# Nguon_MIC_Sch.net
KiCad netlist of a schematic drawn in Altium Designer
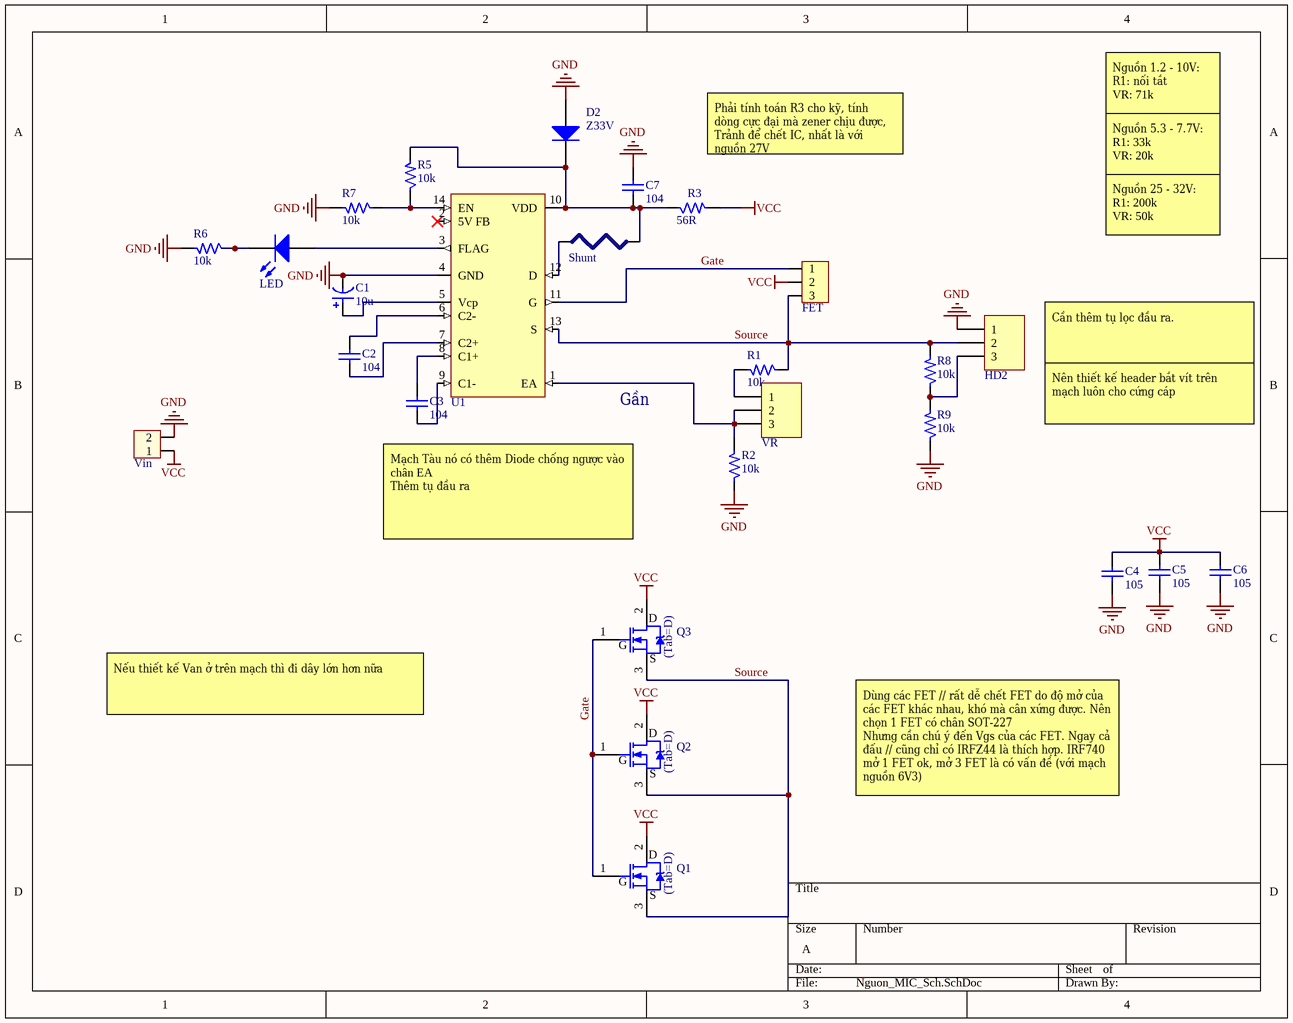
[diagram p0: Nguon_MIC_Sch.SchDoc]

(export (version "E")
  (design (tool "Eeschema 10.0.6"))
  (components
    (comp (ref "C1")
      (value "10u")
      (footprint "C5mm")
      (description "Cap pol")
      (fields (field (name "Comment") "Cap Pol1") (field (name "PUBLISHER") "Altium Limited"))
      (libsource (lib "hienclubvn") (part "Cap Pol"))
    )
    (comp (ref "C2")
      (value "104")
      (footprint "CN1.5")
      (description "Capacitor")
      (fields (field (name "Comment") "Cap") (field (name "PUBLISHER") "Altium Limited"))
      (libsource (lib "hienclubvn") (part "Cap"))
    )
    (comp (ref "C3")
      (value "104")
      (footprint "CN1.5")
      (description "Capacitor")
      (fields (field (name "Comment") "Cap") (field (name "PUBLISHER") "Altium Limited"))
      (libsource (lib "hienclubvn") (part "Cap"))
    )
    (comp (ref "C4")
      (value "105")
      (footprint "CN1.5")
      (description "Capacitor")
      (fields (field (name "Comment") "Cap") (field (name "PUBLISHER") "Altium Limited"))
      (libsource (lib "hienclubvn") (part "Cap"))
    )
    (comp (ref "C5")
      (value "105")
      (footprint "CN1.5")
      (description "Capacitor")
      (fields (field (name "Comment") "Cap") (field (name "PUBLISHER") "Altium Limited"))
      (libsource (lib "hienclubvn") (part "Cap"))
    )
    (comp (ref "C6")
      (value "105")
      (footprint "CN1.5")
      (description "Capacitor")
      (fields (field (name "Comment") "Cap") (field (name "PUBLISHER") "Altium Limited"))
      (libsource (lib "hienclubvn") (part "Cap"))
    )
    (comp (ref "C7")
      (value "104")
      (footprint "CN1.5")
      (description "Capacitor")
      (fields (field (name "Comment") "Cap") (field (name "PUBLISHER") "Altium Limited"))
      (libsource (lib "hienclubvn") (part "Cap"))
    )
    (comp (ref "D2")
      (value "Z33V")
      (footprint "1N4148")
      (description "Default Diode")
      (fields (field (name "PUBLISHER") "Altium Limited"))
      (libsource (lib "hienclubvn") (part "Diode"))
    )
    (comp (ref "FET")
      (value "Header 3")
      (footprint "Header 3 - 150mil")
      (libsource (lib "TIEP2013") (part "Header 3"))
    )
    (comp (ref "HD2")
      (value "Header 3")
      (footprint "BIG_Header 3")
      (description "Header, 3-Pin")
      (fields (field (name "PUBLISHER") "Altium Limited"))
      (libsource (lib "hienclubvn") (part "Header 3"))
    )
    (comp (ref "LED")
      (value "LED SMD")
      (footprint "LED_0805_Blue")
      (description "LED")
      (libsource (lib "PIF_Library") (part "LED SMD"))
    )
    (comp (ref "Q1")
      (value "IRF3205")
      (footprint "TO-220")
      (description "HEXFET N-Channel Power MOSFET")
      (libsource (lib "HIENCLUBVN_Library") (part "IRF3205"))
    )
    (comp (ref "Q2")
      (value "IRF3205")
      (footprint "TO-220")
      (description "HEXFET N-Channel Power MOSFET")
      (libsource (lib "HIENCLUBVN_Library") (part "IRF3205"))
    )
    (comp (ref "Q3")
      (value "IRF3205")
      (footprint "TO-220")
      (description "HEXFET N-Channel Power MOSFET")
      (libsource (lib "HIENCLUBVN_Library") (part "IRF3205"))
    )
    (comp (ref "R1")
      (value "10k")
      (footprint "SM-0805")
      (description "RES SMD 10K OHM 5% 1/8W 0805")
      (fields
        (field (name "MANUFACTURER") "Stackpole Electronics Inc.")
        (field (name "MANUFACTURER PART NUMBER") "RMCF0805JT10K0")
        (field (name "RESISTANCE (OHMS)") "10k")
      )
      (libsource (lib "HIENCLUBVN_Library") (part "RES 0805"))
    )
    (comp (ref "R2")
      (value "10k")
      (footprint "SM-0805")
      (description "RES SMD 10K OHM 5% 1/8W 0805")
      (fields
        (field (name "MANUFACTURER") "Stackpole Electronics Inc.")
        (field (name "MANUFACTURER PART NUMBER") "RMCF0805JT10K0")
        (field (name "RESISTANCE (OHMS)") "10k")
      )
      (libsource (lib "HIENCLUBVN_Library") (part "RES 0805"))
    )
    (comp (ref "R3")
      (value "56R")
      (footprint "R2W")
      (description "RES DIP 10K OHM 5% 1/4W")
      (fields
        (field (name "MANUFACTURER") "Stackpole Electronics Inc.")
        (field (name "MANUFACTURER PART NUMBER") "RMCF0805JT10K0")
        (field (name "RESISTANCE (OHMS)") "56R")
      )
      (libsource (lib "HIENCLUBVN_Library") (part "RES DIP"))
    )
    (comp (ref "R5")
      (value "10k")
      (footprint "SM-0805")
      (description "RES SMD 10K OHM 5% 1/8W 0805")
      (fields
        (field (name "MANUFACTURER") "Stackpole Electronics Inc.")
        (field (name "MANUFACTURER PART NUMBER") "RMCF0805JT10K0")
        (field (name "RESISTANCE (OHMS)") "10k")
      )
      (libsource (lib "HIENCLUBVN_Library") (part "RES 0805"))
    )
    (comp (ref "R6")
      (value "10k")
      (footprint "SM-0805")
      (description "RES SMD 10K OHM 5% 1/8W 0805")
      (fields
        (field (name "MANUFACTURER") "Stackpole Electronics Inc.")
        (field (name "MANUFACTURER PART NUMBER") "RMCF0805JT10K0")
        (field (name "RESISTANCE (OHMS)") "10k")
      )
      (libsource (lib "HIENCLUBVN_Library") (part "RES 0805"))
    )
    (comp (ref "R7")
      (value "10k")
      (footprint "SM-0805")
      (description "RES SMD 10K OHM 5% 1/8W 0805")
      (fields
        (field (name "MANUFACTURER") "Stackpole Electronics Inc.")
        (field (name "MANUFACTURER PART NUMBER") "RMCF0805JT10K0")
        (field (name "RESISTANCE (OHMS)") "10k")
      )
      (libsource (lib "HIENCLUBVN_Library") (part "RES 0805"))
    )
    (comp (ref "R8")
      (value "10k")
      (footprint "SM-0805")
      (description "RES SMD 10K OHM 5% 1/8W 0805")
      (fields
        (field (name "MANUFACTURER") "Stackpole Electronics Inc.")
        (field (name "MANUFACTURER PART NUMBER") "RMCF0805JT10K0")
        (field (name "RESISTANCE (OHMS)") "10k")
      )
      (libsource (lib "HIENCLUBVN_Library") (part "RES 0805"))
    )
    (comp (ref "R9")
      (value "10k")
      (footprint "SM-0805")
      (description "RES SMD 10K OHM 5% 1/8W 0805")
      (fields
        (field (name "MANUFACTURER") "Stackpole Electronics Inc.")
        (field (name "MANUFACTURER PART NUMBER") "RMCF0805JT10K0")
        (field (name "RESISTANCE (OHMS)") "10k")
      )
      (libsource (lib "HIENCLUBVN_Library") (part "RES 0805"))
    )
    (comp (ref "Shunt") (value "Shunt") (footprint "Shunt 5mR") (libsource (lib "TIEP2013") (part "Shunt")))
    (comp (ref "U1")
      (value "MIC5158")
      (footprint "SOIC14")
      (description "Super LDO")
      (libsource (lib "TIEP2013") (part "MIC5158"))
    )
    (comp (ref "Vin")
      (value "Header 2")
      (footprint "HEAD2T")
      (description "Header, 2-Pin")
      (libsource (lib "hienclubvn") (part "Header 2"))
    )
    (comp (ref "VR")
      (value "Header 3")
      (footprint "BIG_Header 3")
      (description "Header, 3-Pin")
      (fields (field (name "PUBLISHER") "Altium Limited"))
      (libsource (lib "hienclubvn") (part "Header 3"))
    )
  )
  (nets
    (net (code "1") (name "/Gate") (class "Default")
      (node (ref "FET") (pin "1") (pinfunction "1_1") (pintype "passive"))
      (node (ref "Q1") (pin "1") (pinfunction "G_1") (pintype "passive"))
      (node (ref "Q2") (pin "1") (pinfunction "G_1") (pintype "passive"))
      (node (ref "Q3") (pin "1") (pinfunction "G_1") (pintype "passive"))
      (node (ref "U1") (pin "11") (pinfunction "G_11") (pintype "output"))
    )
    (net (code "2") (name "/Source") (class "Default")
      (node (ref "FET") (pin "3") (pinfunction "3_3") (pintype "passive"))
      (node (ref "HD2") (pin "2") (pinfunction "2_2") (pintype "passive"))
      (node (ref "Q1") (pin "3") (pinfunction "S_3") (pintype "passive"))
      (node (ref "Q2") (pin "3") (pinfunction "S_3") (pintype "passive"))
      (node (ref "Q3") (pin "3") (pinfunction "S_3") (pintype "passive"))
      (node (ref "R1") (pin "1") (pinfunction "1_1") (pintype "passive"))
      (node (ref "R8") (pin "2") (pinfunction "2_2") (pintype "passive"))
      (node (ref "U1") (pin "13") (pinfunction "S_13") (pintype "input"))
    )
    (net (code "3") (name "GND") (class "Default")
      (node (ref "C1") (pin "2") (pinfunction "2_2") (pintype "passive"))
      (node (ref "C4") (pin "1") (pinfunction "1_1") (pintype "passive"))
      (node (ref "C5") (pin "1") (pinfunction "1_1") (pintype "passive"))
      (node (ref "C6") (pin "1") (pinfunction "1_1") (pintype "passive"))
      (node (ref "C7") (pin "2") (pinfunction "2_2") (pintype "passive"))
      (node (ref "D2") (pin "1") (pinfunction "A_1") (pintype "passive"))
      (node (ref "HD2") (pin "1") (pinfunction "1_1") (pintype "passive"))
      (node (ref "R2") (pin "1") (pinfunction "1_1") (pintype "passive"))
      (node (ref "R6") (pin "2") (pinfunction "2_2") (pintype "passive"))
      (node (ref "R7") (pin "2") (pinfunction "2_2") (pintype "passive"))
      (node (ref "R9") (pin "1") (pinfunction "1_1") (pintype "passive"))
      (node (ref "U1") (pin "4") (pinfunction "GND_4") (pintype "power_in"))
      (node (ref "Vin") (pin "2") (pinfunction "2_2") (pintype "passive"))
    )
    (net (code "4") (name "Net-(D2-K)") (class "Default")
      (node (ref "C7") (pin "1") (pinfunction "1_1") (pintype "passive"))
      (node (ref "D2") (pin "2") (pinfunction "K_2") (pintype "passive"))
      (node (ref "R3") (pin "1") (pinfunction "1_1") (pintype "passive"))
      (node (ref "R5") (pin "2") (pinfunction "2_2") (pintype "passive"))
      (node (ref "Shunt") (pin "1") (pinfunction "1_1") (pintype "passive"))
      (node (ref "U1") (pin "10") (pinfunction "VDD_10") (pintype "power_in"))
    )
    (net (code "5") (name "Net-(HD2-Pad3)") (class "Default")
      (node (ref "HD2") (pin "3") (pinfunction "3_3") (pintype "passive"))
      (node (ref "R8") (pin "1") (pinfunction "1_1") (pintype "passive"))
      (node (ref "R9") (pin "2") (pinfunction "2_2") (pintype "passive"))
    )
    (net (code "6") (name "Net-(LED-A)") (class "Default")
      (node (ref "LED") (pin "1") (pinfunction "A_1") (pintype "passive"))
      (node (ref "U1") (pin "3") (pinfunction "FLAG_3") (pintype "output"))
    )
    (net (code "7") (name "Net-(LED-K)") (class "Default")
      (node (ref "LED") (pin "2") (pinfunction "K_2") (pintype "passive"))
      (node (ref "R6") (pin "1") (pinfunction "1_1") (pintype "passive"))
    )
    (net (code "8") (name "Net-(R1-Pad2)") (class "Default")
      (node (ref "R1") (pin "2") (pinfunction "2_2") (pintype "passive"))
      (node (ref "VR") (pin "1") (pinfunction "1_1") (pintype "passive"))
    )
    (net (code "9") (name "Net-(U1-C1+)") (class "Default")
      (node (ref "C3") (pin "2") (pinfunction "2_2") (pintype "passive"))
      (node (ref "U1") (pin "8") (pinfunction "C1+_8") (pintype "input"))
    )
    (net (code "10") (name "Net-(U1-C1-)") (class "Default")
      (node (ref "C3") (pin "1") (pinfunction "1_1") (pintype "passive"))
      (node (ref "U1") (pin "9") (pinfunction "C1-_9") (pintype "input"))
    )
    (net (code "11") (name "Net-(U1-C2+)") (class "Default")
      (node (ref "C2") (pin "1") (pinfunction "1_1") (pintype "passive"))
      (node (ref "U1") (pin "7") (pinfunction "C2+_7") (pintype "input"))
    )
    (net (code "12") (name "Net-(U1-C2-)") (class "Default")
      (node (ref "C2") (pin "2") (pinfunction "2_2") (pintype "passive"))
      (node (ref "U1") (pin "6") (pinfunction "C2-_6") (pintype "input"))
    )
    (net (code "13") (name "Net-(U1-D)") (class "Default")
      (node (ref "Shunt") (pin "2") (pinfunction "2_2") (pintype "passive"))
      (node (ref "U1") (pin "12") (pinfunction "D_12") (pintype "input"))
    )
    (net (code "14") (name "Net-(U1-EA)") (class "Default")
      (node (ref "R2") (pin "2") (pinfunction "2_2") (pintype "passive"))
      (node (ref "U1") (pin "1") (pinfunction "EA_1") (pintype "input"))
      (node (ref "VR") (pin "2") (pinfunction "2_2") (pintype "passive"))
      (node (ref "VR") (pin "3") (pinfunction "3_3") (pintype "passive"))
    )
    (net (code "15") (name "Net-(U1-EN)") (class "Default")
      (node (ref "R5") (pin "1") (pinfunction "1_1") (pintype "passive"))
      (node (ref "R7") (pin "1") (pinfunction "1_1") (pintype "passive"))
      (node (ref "U1") (pin "14") (pinfunction "EN_14") (pintype "input"))
    )
    (net (code "16") (name "Net-(U1-Vcp)") (class "Default")
      (node (ref "C1") (pin "1") (pinfunction "1_1") (pintype "passive"))
      (node (ref "U1") (pin "5") (pinfunction "Vcp_5") (pintype "power_in"))
    )
    (net (code "17") (name "VCC") (class "Default")
      (node (ref "C4") (pin "2") (pinfunction "2_2") (pintype "passive"))
      (node (ref "C5") (pin "2") (pinfunction "2_2") (pintype "passive"))
      (node (ref "C6") (pin "2") (pinfunction "2_2") (pintype "passive"))
      (node (ref "FET") (pin "2") (pinfunction "2_2") (pintype "passive"))
      (node (ref "Q1") (pin "2") (pinfunction "D_2") (pintype "passive"))
      (node (ref "Q2") (pin "2") (pinfunction "D_2") (pintype "passive"))
      (node (ref "Q3") (pin "2") (pinfunction "D_2") (pintype "passive"))
      (node (ref "R3") (pin "2") (pinfunction "2_2") (pintype "passive"))
      (node (ref "Vin") (pin "1") (pinfunction "1_1") (pintype "passive"))
    )
    (net (code "18") (name "unconnected-(U1-5V_FB-Pad2)") (class "Default")
      (node (ref "U1") (pin "2") (pinfunction "5V_FB_2") (pintype "input+no_connect"))
    )
  )
)
